# FPGA_PWR.net
KiCad netlist of a schematic drawn in Altium Designer
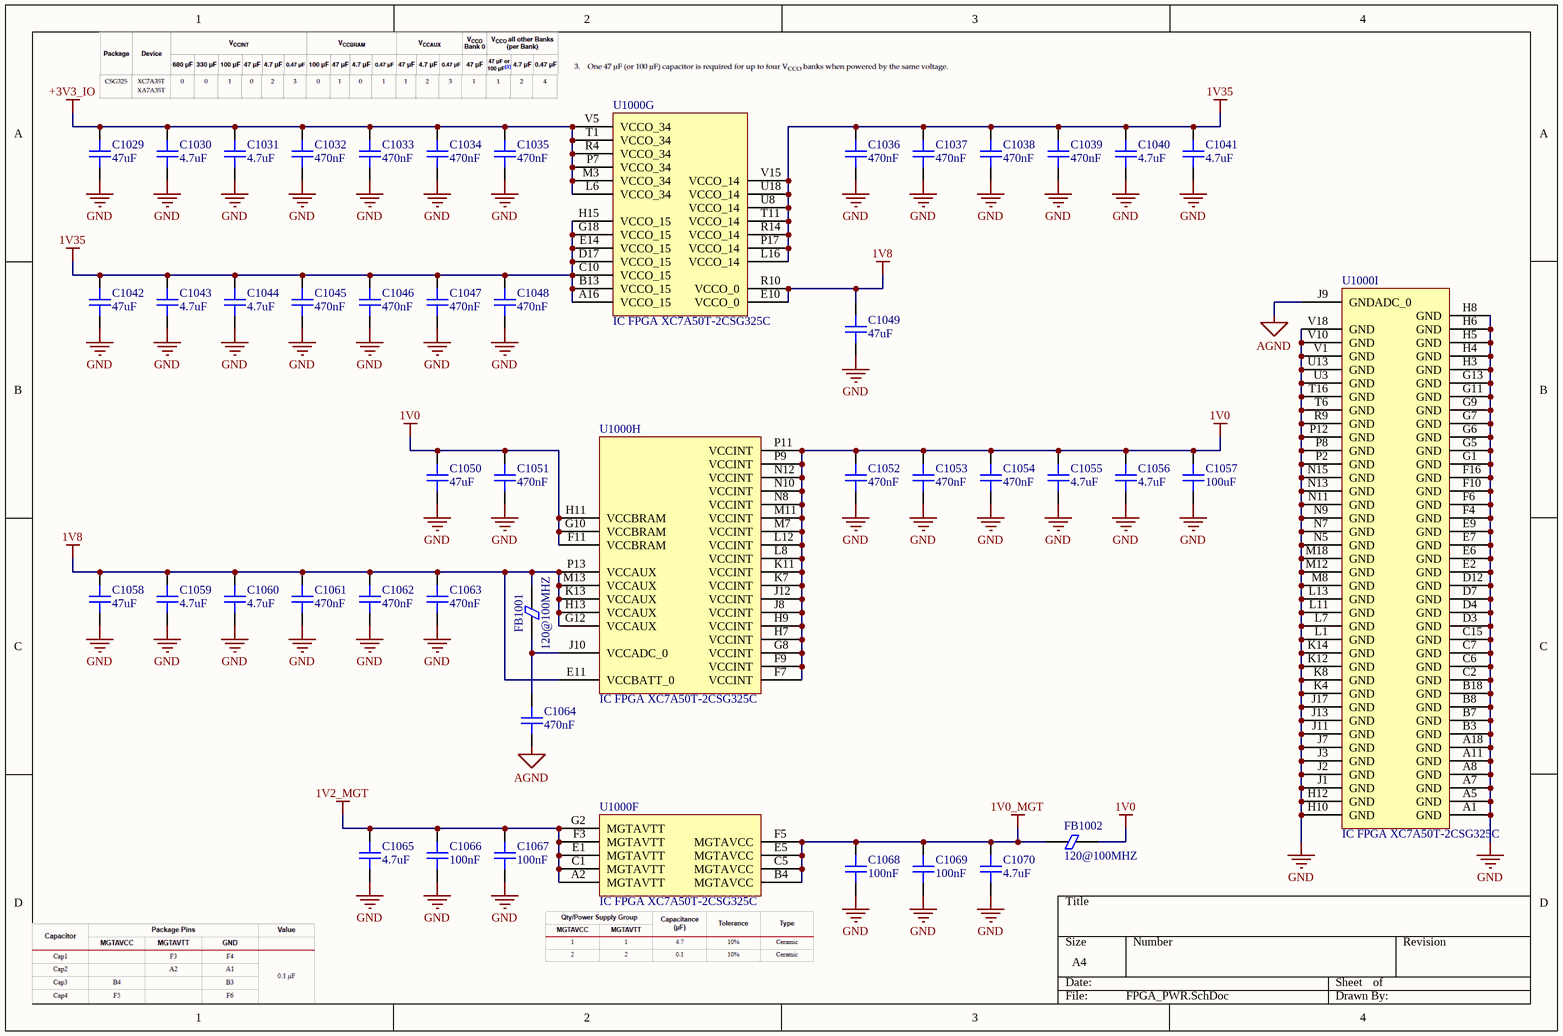
[diagram p0: FPGA_PWR.SchDoc]

(export (version "E")
  (design (tool "Eeschema 10.0.6"))
  (components
    (comp (ref "C1029")
      (value "47uF")
      (footprint "GEN_C_0805")
      (fields
        (field (name "HOUSE PART NUMBER") "C-47uF-0805-002")
        (field (name "MANUFACTURER") "Samsung")
        (field (name "MANUFACTURER PART NUMBER") "CL21A476MQYNNNE")
      )
      (libsource (lib "DSO") (part "CAP 47uF 6.3V X5R 0805"))
    )
    (comp (ref "C1030")
      (value "4.7uF")
      (footprint "GEN_C_0402")
      (fields
        (field (name "HOUSE PART NUMBER") "C-4.7uF-0402-002")
        (field (name "MANUFACTURER") "Murata")
        (field (name "MANUFACTURER PART NUMBER") "GRM155R60J475ME47D")
      )
      (libsource (lib "DSO") (part "CAP 4.7uF 6.3V X5R 0402"))
    )
    (comp (ref "C1031")
      (value "4.7uF")
      (footprint "GEN_C_0402")
      (fields
        (field (name "HOUSE PART NUMBER") "C-4.7uF-0402-002")
        (field (name "MANUFACTURER") "Murata")
        (field (name "MANUFACTURER PART NUMBER") "GRM155R60J475ME47D")
      )
      (libsource (lib "DSO") (part "CAP 4.7uF 6.3V X5R 0402"))
    )
    (comp (ref "C1032")
      (value "470nF")
      (footprint "GEN_C_0201")
      (fields
        (field (name "HOUSE PART NUMBER") "C-470nF-0201-002")
        (field (name "MANUFACTURER") "Murata")
        (field (name "MANUFACTURER PART NUMBER") "GRM033R60J474KE90D")
      )
      (libsource (lib "DSO") (part "CAP 470nF 6.3V X5R 0201"))
    )
    (comp (ref "C1033")
      (value "470nF")
      (footprint "GEN_C_0201")
      (fields
        (field (name "HOUSE PART NUMBER") "C-470nF-0201-002")
        (field (name "MANUFACTURER") "Murata")
        (field (name "MANUFACTURER PART NUMBER") "GRM033R60J474KE90D")
      )
      (libsource (lib "DSO") (part "CAP 470nF 6.3V X5R 0201"))
    )
    (comp (ref "C1034")
      (value "470nF")
      (footprint "GEN_C_0201")
      (fields
        (field (name "HOUSE PART NUMBER") "C-470nF-0201-002")
        (field (name "MANUFACTURER") "Murata")
        (field (name "MANUFACTURER PART NUMBER") "GRM033R60J474KE90D")
      )
      (libsource (lib "DSO") (part "CAP 470nF 6.3V X5R 0201"))
    )
    (comp (ref "C1035")
      (value "470nF")
      (footprint "GEN_C_0201")
      (fields
        (field (name "HOUSE PART NUMBER") "C-470nF-0201-002")
        (field (name "MANUFACTURER") "Murata")
        (field (name "MANUFACTURER PART NUMBER") "GRM033R60J474KE90D")
      )
      (libsource (lib "DSO") (part "CAP 470nF 6.3V X5R 0201"))
    )
    (comp (ref "C1036")
      (value "470nF")
      (footprint "GEN_C_0201")
      (fields
        (field (name "HOUSE PART NUMBER") "C-470nF-0201-002")
        (field (name "MANUFACTURER") "Murata")
        (field (name "MANUFACTURER PART NUMBER") "GRM033R60J474KE90D")
      )
      (libsource (lib "DSO") (part "CAP 470nF 6.3V X5R 0201"))
    )
    (comp (ref "C1037")
      (value "470nF")
      (footprint "GEN_C_0201")
      (fields
        (field (name "HOUSE PART NUMBER") "C-470nF-0201-002")
        (field (name "MANUFACTURER") "Murata")
        (field (name "MANUFACTURER PART NUMBER") "GRM033R60J474KE90D")
      )
      (libsource (lib "DSO") (part "CAP 470nF 6.3V X5R 0201"))
    )
    (comp (ref "C1038")
      (value "470nF")
      (footprint "GEN_C_0201")
      (fields
        (field (name "HOUSE PART NUMBER") "C-470nF-0201-002")
        (field (name "MANUFACTURER") "Murata")
        (field (name "MANUFACTURER PART NUMBER") "GRM033R60J474KE90D")
      )
      (libsource (lib "DSO") (part "CAP 470nF 6.3V X5R 0201"))
    )
    (comp (ref "C1039")
      (value "470nF")
      (footprint "GEN_C_0201")
      (fields
        (field (name "HOUSE PART NUMBER") "C-470nF-0201-002")
        (field (name "MANUFACTURER") "Murata")
        (field (name "MANUFACTURER PART NUMBER") "GRM033R60J474KE90D")
      )
      (libsource (lib "DSO") (part "CAP 470nF 6.3V X5R 0201"))
    )
    (comp (ref "C1040")
      (value "4.7uF")
      (footprint "GEN_C_0402")
      (fields
        (field (name "HOUSE PART NUMBER") "C-4.7uF-0402-002")
        (field (name "MANUFACTURER") "Murata")
        (field (name "MANUFACTURER PART NUMBER") "GRM155R60J475ME47D")
      )
      (libsource (lib "DSO") (part "CAP 4.7uF 6.3V X5R 0402"))
    )
    (comp (ref "C1041")
      (value "4.7uF")
      (footprint "GEN_C_0402")
      (fields
        (field (name "HOUSE PART NUMBER") "C-4.7uF-0402-002")
        (field (name "MANUFACTURER") "Murata")
        (field (name "MANUFACTURER PART NUMBER") "GRM155R60J475ME47D")
      )
      (libsource (lib "DSO") (part "CAP 4.7uF 6.3V X5R 0402"))
    )
    (comp (ref "C1042")
      (value "47uF")
      (footprint "GEN_C_0805")
      (fields
        (field (name "HOUSE PART NUMBER") "C-47uF-0805-002")
        (field (name "MANUFACTURER") "Samsung")
        (field (name "MANUFACTURER PART NUMBER") "CL21A476MQYNNNE")
      )
      (libsource (lib "DSO") (part "CAP 47uF 6.3V X5R 0805"))
    )
    (comp (ref "C1043")
      (value "4.7uF")
      (footprint "GEN_C_0402")
      (fields
        (field (name "HOUSE PART NUMBER") "C-4.7uF-0402-002")
        (field (name "MANUFACTURER") "Murata")
        (field (name "MANUFACTURER PART NUMBER") "GRM155R60J475ME47D")
      )
      (libsource (lib "DSO") (part "CAP 4.7uF 6.3V X5R 0402"))
    )
    (comp (ref "C1044")
      (value "4.7uF")
      (footprint "GEN_C_0402")
      (fields
        (field (name "HOUSE PART NUMBER") "C-4.7uF-0402-002")
        (field (name "MANUFACTURER") "Murata")
        (field (name "MANUFACTURER PART NUMBER") "GRM155R60J475ME47D")
      )
      (libsource (lib "DSO") (part "CAP 4.7uF 6.3V X5R 0402"))
    )
    (comp (ref "C1045")
      (value "470nF")
      (footprint "GEN_C_0201")
      (fields
        (field (name "HOUSE PART NUMBER") "C-470nF-0201-002")
        (field (name "MANUFACTURER") "Murata")
        (field (name "MANUFACTURER PART NUMBER") "GRM033R60J474KE90D")
      )
      (libsource (lib "DSO") (part "CAP 470nF 6.3V X5R 0201"))
    )
    (comp (ref "C1046")
      (value "470nF")
      (footprint "GEN_C_0201")
      (fields
        (field (name "HOUSE PART NUMBER") "C-470nF-0201-002")
        (field (name "MANUFACTURER") "Murata")
        (field (name "MANUFACTURER PART NUMBER") "GRM033R60J474KE90D")
      )
      (libsource (lib "DSO") (part "CAP 470nF 6.3V X5R 0201"))
    )
    (comp (ref "C1047")
      (value "470nF")
      (footprint "GEN_C_0201")
      (fields
        (field (name "HOUSE PART NUMBER") "C-470nF-0201-002")
        (field (name "MANUFACTURER") "Murata")
        (field (name "MANUFACTURER PART NUMBER") "GRM033R60J474KE90D")
      )
      (libsource (lib "DSO") (part "CAP 470nF 6.3V X5R 0201"))
    )
    (comp (ref "C1048")
      (value "470nF")
      (footprint "GEN_C_0201")
      (fields
        (field (name "HOUSE PART NUMBER") "C-470nF-0201-002")
        (field (name "MANUFACTURER") "Murata")
        (field (name "MANUFACTURER PART NUMBER") "GRM033R60J474KE90D")
      )
      (libsource (lib "DSO") (part "CAP 470nF 6.3V X5R 0201"))
    )
    (comp (ref "C1049")
      (value "47uF")
      (footprint "GEN_C_0805")
      (fields
        (field (name "HOUSE PART NUMBER") "C-47uF-0805-002")
        (field (name "MANUFACTURER") "Samsung")
        (field (name "MANUFACTURER PART NUMBER") "CL21A476MQYNNNE")
      )
      (libsource (lib "DSO") (part "CAP 47uF 6.3V X5R 0805"))
    )
    (comp (ref "C1050")
      (value "47uF")
      (footprint "GEN_C_0805")
      (fields
        (field (name "HOUSE PART NUMBER") "C-47uF-0805-002")
        (field (name "MANUFACTURER") "Samsung")
        (field (name "MANUFACTURER PART NUMBER") "CL21A476MQYNNNE")
      )
      (libsource (lib "DSO") (part "CAP 47uF 6.3V X5R 0805"))
    )
    (comp (ref "C1051")
      (value "470nF")
      (footprint "GEN_C_0201")
      (fields
        (field (name "HOUSE PART NUMBER") "C-470nF-0201-002")
        (field (name "MANUFACTURER") "Murata")
        (field (name "MANUFACTURER PART NUMBER") "GRM033R60J474KE90D")
      )
      (libsource (lib "DSO") (part "CAP 470nF 6.3V X5R 0201"))
    )
    (comp (ref "C1052")
      (value "470nF")
      (footprint "GEN_C_0201")
      (fields
        (field (name "HOUSE PART NUMBER") "C-470nF-0201-002")
        (field (name "MANUFACTURER") "Murata")
        (field (name "MANUFACTURER PART NUMBER") "GRM033R60J474KE90D")
      )
      (libsource (lib "DSO") (part "CAP 470nF 6.3V X5R 0201"))
    )
    (comp (ref "C1053")
      (value "470nF")
      (footprint "GEN_C_0201")
      (fields
        (field (name "HOUSE PART NUMBER") "C-470nF-0201-002")
        (field (name "MANUFACTURER") "Murata")
        (field (name "MANUFACTURER PART NUMBER") "GRM033R60J474KE90D")
      )
      (libsource (lib "DSO") (part "CAP 470nF 6.3V X5R 0201"))
    )
    (comp (ref "C1054")
      (value "470nF")
      (footprint "GEN_C_0201")
      (fields
        (field (name "HOUSE PART NUMBER") "C-470nF-0201-002")
        (field (name "MANUFACTURER") "Murata")
        (field (name "MANUFACTURER PART NUMBER") "GRM033R60J474KE90D")
      )
      (libsource (lib "DSO") (part "CAP 470nF 6.3V X5R 0201"))
    )
    (comp (ref "C1055")
      (value "4.7uF")
      (footprint "GEN_C_0402")
      (fields
        (field (name "HOUSE PART NUMBER") "C-4.7uF-0402-002")
        (field (name "MANUFACTURER") "Murata")
        (field (name "MANUFACTURER PART NUMBER") "GRM155R60J475ME47D")
      )
      (libsource (lib "DSO") (part "CAP 4.7uF 6.3V X5R 0402"))
    )
    (comp (ref "C1056")
      (value "4.7uF")
      (footprint "GEN_C_0402")
      (fields
        (field (name "HOUSE PART NUMBER") "C-4.7uF-0402-002")
        (field (name "MANUFACTURER") "Murata")
        (field (name "MANUFACTURER PART NUMBER") "GRM155R60J475ME47D")
      )
      (libsource (lib "DSO") (part "CAP 4.7uF 6.3V X5R 0402"))
    )
    (comp (ref "C1057")
      (value "100uF")
      (footprint "GEN_C_1210")
      (fields
        (field (name "HOUSE PART NUMBER") "C-100uF-1210-002")
        (field (name "MANUFACTURER") "Samsung")
        (field (name "MANUFACTURER PART NUMBER") "CL32A107MQVNNNE")
      )
      (libsource (lib "DSO") (part "CAP 100uF 6.3V X5R 1210"))
    )
    (comp (ref "C1058")
      (value "47uF")
      (footprint "GEN_C_0805")
      (fields
        (field (name "HOUSE PART NUMBER") "C-47uF-0805-002")
        (field (name "MANUFACTURER") "Samsung")
        (field (name "MANUFACTURER PART NUMBER") "CL21A476MQYNNNE")
      )
      (libsource (lib "DSO") (part "CAP 47uF 6.3V X5R 0805"))
    )
    (comp (ref "C1059")
      (value "4.7uF")
      (footprint "GEN_C_0402")
      (fields
        (field (name "HOUSE PART NUMBER") "C-4.7uF-0402-002")
        (field (name "MANUFACTURER") "Murata")
        (field (name "MANUFACTURER PART NUMBER") "GRM155R60J475ME47D")
      )
      (libsource (lib "DSO") (part "CAP 4.7uF 6.3V X5R 0402"))
    )
    (comp (ref "C1060")
      (value "4.7uF")
      (footprint "GEN_C_0402")
      (fields
        (field (name "HOUSE PART NUMBER") "C-4.7uF-0402-002")
        (field (name "MANUFACTURER") "Murata")
        (field (name "MANUFACTURER PART NUMBER") "GRM155R60J475ME47D")
      )
      (libsource (lib "DSO") (part "CAP 4.7uF 6.3V X5R 0402"))
    )
    (comp (ref "C1061")
      (value "470nF")
      (footprint "GEN_C_0201")
      (fields
        (field (name "HOUSE PART NUMBER") "C-470nF-0201-002")
        (field (name "MANUFACTURER") "Murata")
        (field (name "MANUFACTURER PART NUMBER") "GRM033R60J474KE90D")
      )
      (libsource (lib "DSO") (part "CAP 470nF 6.3V X5R 0201"))
    )
    (comp (ref "C1062")
      (value "470nF")
      (footprint "GEN_C_0201")
      (fields
        (field (name "HOUSE PART NUMBER") "C-470nF-0201-002")
        (field (name "MANUFACTURER") "Murata")
        (field (name "MANUFACTURER PART NUMBER") "GRM033R60J474KE90D")
      )
      (libsource (lib "DSO") (part "CAP 470nF 6.3V X5R 0201"))
    )
    (comp (ref "C1063")
      (value "470nF")
      (footprint "GEN_C_0201")
      (fields
        (field (name "HOUSE PART NUMBER") "C-470nF-0201-002")
        (field (name "MANUFACTURER") "Murata")
        (field (name "MANUFACTURER PART NUMBER") "GRM033R60J474KE90D")
      )
      (libsource (lib "DSO") (part "CAP 470nF 6.3V X5R 0201"))
    )
    (comp (ref "C1064")
      (value "470nF")
      (footprint "GEN_C_0201")
      (fields
        (field (name "HOUSE PART NUMBER") "C-470nF-0201-002")
        (field (name "MANUFACTURER") "Murata")
        (field (name "MANUFACTURER PART NUMBER") "GRM033R60J474KE90D")
      )
      (libsource (lib "DSO") (part "CAP 470nF 6.3V X5R 0201"))
    )
    (comp (ref "C1065")
      (value "4.7uF")
      (footprint "GEN_C_0402")
      (fields
        (field (name "HOUSE PART NUMBER") "C-4.7uF-0402-002")
        (field (name "MANUFACTURER") "Murata")
        (field (name "MANUFACTURER PART NUMBER") "GRM155R60J475ME47D")
      )
      (libsource (lib "DSO") (part "CAP 4.7uF 6.3V X5R 0402"))
    )
    (comp (ref "C1066")
      (value "100nF")
      (footprint "GEN_C_0201")
      (fields
        (field (name "HOUSE PART NUMBER") "C-100nF-0201-002")
        (field (name "MANUFACTURER") "Murata")
        (field (name "MANUFACTURER PART NUMBER") "GRM033R60J104KE19D")
      )
      (libsource (lib "DSO") (part "CAP 100nF 6.3V X5R 0201"))
    )
    (comp (ref "C1067")
      (value "100nF")
      (footprint "GEN_C_0201")
      (fields
        (field (name "HOUSE PART NUMBER") "C-100nF-0201-002")
        (field (name "MANUFACTURER") "Murata")
        (field (name "MANUFACTURER PART NUMBER") "GRM033R60J104KE19D")
      )
      (libsource (lib "DSO") (part "CAP 100nF 6.3V X5R 0201"))
    )
    (comp (ref "C1068")
      (value "100nF")
      (footprint "GEN_C_0201")
      (fields
        (field (name "HOUSE PART NUMBER") "C-100nF-0201-002")
        (field (name "MANUFACTURER") "Murata")
        (field (name "MANUFACTURER PART NUMBER") "GRM033R60J104KE19D")
      )
      (libsource (lib "DSO") (part "CAP 100nF 6.3V X5R 0201"))
    )
    (comp (ref "C1069")
      (value "100nF")
      (footprint "GEN_C_0201")
      (fields
        (field (name "HOUSE PART NUMBER") "C-100nF-0201-002")
        (field (name "MANUFACTURER") "Murata")
        (field (name "MANUFACTURER PART NUMBER") "GRM033R60J104KE19D")
      )
      (libsource (lib "DSO") (part "CAP 100nF 6.3V X5R 0201"))
    )
    (comp (ref "C1070")
      (value "4.7uF")
      (footprint "GEN_C_0402")
      (fields
        (field (name "HOUSE PART NUMBER") "C-4.7uF-0402-002")
        (field (name "MANUFACTURER") "Murata")
        (field (name "MANUFACTURER PART NUMBER") "GRM155R60J475ME47D")
      )
      (libsource (lib "DSO") (part "CAP 4.7uF 6.3V X5R 0402"))
    )
    (comp (ref "FB1001")
      (value "120@100MHZ")
      (footprint "GEN_R_0402")
      (fields (field (name "HOUSE PART NUMBER") "BLM15PX121SN1D") (field (name "MANUFACTURER") "Murata"))
      (libsource (lib "DSO") (part "FERRITE BEAD 120 OHM 0402"))
    )
    (comp (ref "FB1002")
      (value "120@100MHZ")
      (footprint "GEN_R_0402")
      (fields (field (name "HOUSE PART NUMBER") "BLM15PX121SN1D") (field (name "MANUFACTURER") "Murata"))
      (libsource (lib "DSO") (part "FERRITE BEAD 120 OHM 0402"))
    )
    (comp (ref "U1000")
      (value "IC FPGA XC7A50T-2CSG325C")
      (footprint "XILINX_XC7A50T-2CSG325C")
      (description "Artix-7 FPGA, 150 User I/Os, 4 GTP, 324-Ball BGA, Speed Grade 2, Commercial Grade, Pb-Free")
      (fields (field (name "MANUFACTURER") "Xilinx") (field (name "HOUSE PART NUMBER") "XC7A50T-2CSG325C"))
      (libsource (lib "DSO") (part "IC FPGA XC7A50T-2CSG325C"))
    )
  )
  (nets
    (net (code "1") (name "+3V3_IO") (class "Default")
      (node (ref "C1029") (pin "2") (pinfunction "2_2") (pintype "passive"))
      (node (ref "C1030") (pin "2") (pinfunction "2_2") (pintype "passive"))
      (node (ref "C1031") (pin "2") (pinfunction "2_2") (pintype "passive"))
      (node (ref "C1032") (pin "2") (pinfunction "2_2") (pintype "passive"))
      (node (ref "C1033") (pin "2") (pinfunction "2_2") (pintype "passive"))
      (node (ref "C1034") (pin "2") (pinfunction "2_2") (pintype "passive"))
      (node (ref "C1035") (pin "2") (pinfunction "2_2") (pintype "passive"))
      (node (ref "U1000") (pin "L6") (pinfunction "VCCO_34_L6") (pintype "power_in"))
      (node (ref "U1000") (pin "M3") (pinfunction "VCCO_34_M3") (pintype "power_in"))
      (node (ref "U1000") (pin "P7") (pinfunction "VCCO_34_P7") (pintype "power_in"))
      (node (ref "U1000") (pin "R4") (pinfunction "VCCO_34_R4") (pintype "power_in"))
      (node (ref "U1000") (pin "T1") (pinfunction "VCCO_34_T1") (pintype "power_in"))
      (node (ref "U1000") (pin "V5") (pinfunction "VCCO_34_V5") (pintype "power_in"))
    )
    (net (code "2") (name "1V0") (class "Default")
      (node (ref "C1050") (pin "2") (pinfunction "2_2") (pintype "passive"))
      (node (ref "C1051") (pin "2") (pinfunction "2_2") (pintype "passive"))
      (node (ref "C1052") (pin "2") (pinfunction "2_2") (pintype "passive"))
      (node (ref "C1053") (pin "2") (pinfunction "2_2") (pintype "passive"))
      (node (ref "C1054") (pin "2") (pinfunction "2_2") (pintype "passive"))
      (node (ref "C1055") (pin "2") (pinfunction "2_2") (pintype "passive"))
      (node (ref "C1056") (pin "2") (pinfunction "2_2") (pintype "passive"))
      (node (ref "C1057") (pin "2") (pinfunction "2_2") (pintype "passive"))
      (node (ref "FB1002") (pin "1") (pinfunction "1_1") (pintype "passive"))
      (node (ref "U1000") (pin "F11") (pinfunction "VCCBRAM_F11") (pintype "power_in"))
      (node (ref "U1000") (pin "F7") (pinfunction "VCCINT_F7") (pintype "power_in"))
      (node (ref "U1000") (pin "F9") (pinfunction "VCCINT_F9") (pintype "power_in"))
      (node (ref "U1000") (pin "G10") (pinfunction "VCCBRAM_G10") (pintype "power_in"))
      (node (ref "U1000") (pin "G8") (pinfunction "VCCINT_G8") (pintype "power_in"))
      (node (ref "U1000") (pin "H11") (pinfunction "VCCBRAM_H11") (pintype "power_in"))
      (node (ref "U1000") (pin "H7") (pinfunction "VCCINT_H7") (pintype "power_in"))
      (node (ref "U1000") (pin "H9") (pinfunction "VCCINT_H9") (pintype "power_in"))
      (node (ref "U1000") (pin "J12") (pinfunction "VCCINT_J12") (pintype "power_in"))
      (node (ref "U1000") (pin "J8") (pinfunction "VCCINT_J8") (pintype "power_in"))
      (node (ref "U1000") (pin "K11") (pinfunction "VCCINT_K11") (pintype "power_in"))
      (node (ref "U1000") (pin "K7") (pinfunction "VCCINT_K7") (pintype "power_in"))
      (node (ref "U1000") (pin "L12") (pinfunction "VCCINT_L12") (pintype "power_in"))
      (node (ref "U1000") (pin "L8") (pinfunction "VCCINT_L8") (pintype "power_in"))
      (node (ref "U1000") (pin "M11") (pinfunction "VCCINT_M11") (pintype "power_in"))
      (node (ref "U1000") (pin "M7") (pinfunction "VCCINT_M7") (pintype "power_in"))
      (node (ref "U1000") (pin "N10") (pinfunction "VCCINT_N10") (pintype "power_in"))
      (node (ref "U1000") (pin "N12") (pinfunction "VCCINT_N12") (pintype "power_in"))
      (node (ref "U1000") (pin "N8") (pinfunction "VCCINT_N8") (pintype "power_in"))
      (node (ref "U1000") (pin "P11") (pinfunction "VCCINT_P11") (pintype "power_in"))
      (node (ref "U1000") (pin "P9") (pinfunction "VCCINT_P9") (pintype "power_in"))
    )
    (net (code "3") (name "1V0_MGT") (class "Default")
      (node (ref "C1068") (pin "2") (pinfunction "2_2") (pintype "passive"))
      (node (ref "C1069") (pin "2") (pinfunction "2_2") (pintype "passive"))
      (node (ref "C1070") (pin "2") (pinfunction "2_2") (pintype "passive"))
      (node (ref "FB1002") (pin "2") (pinfunction "2_2") (pintype "passive"))
      (node (ref "U1000") (pin "B4") (pinfunction "MGTAVCC_B4") (pintype "power_in"))
      (node (ref "U1000") (pin "C5") (pinfunction "MGTAVCC_C5") (pintype "power_in"))
      (node (ref "U1000") (pin "E5") (pinfunction "MGTAVCC_E5") (pintype "power_in"))
      (node (ref "U1000") (pin "F5") (pinfunction "MGTAVCC_F5") (pintype "power_in"))
    )
    (net (code "4") (name "1V2_MGT") (class "Default")
      (node (ref "C1065") (pin "2") (pinfunction "2_2") (pintype "passive"))
      (node (ref "C1066") (pin "2") (pinfunction "2_2") (pintype "passive"))
      (node (ref "C1067") (pin "2") (pinfunction "2_2") (pintype "passive"))
      (node (ref "U1000") (pin "A2") (pinfunction "MGTAVTT_A2") (pintype "power_in"))
      (node (ref "U1000") (pin "C1") (pinfunction "MGTAVTT_C1") (pintype "power_in"))
      (node (ref "U1000") (pin "E1") (pinfunction "MGTAVTT_E1") (pintype "power_in"))
      (node (ref "U1000") (pin "F3") (pinfunction "MGTAVTT_F3") (pintype "power_in"))
      (node (ref "U1000") (pin "G2") (pinfunction "MGTAVTT_G2") (pintype "power_in"))
    )
    (net (code "5") (name "1V8") (class "Default")
      (node (ref "C1049") (pin "2") (pinfunction "2_2") (pintype "passive"))
      (node (ref "C1058") (pin "2") (pinfunction "2_2") (pintype "passive"))
      (node (ref "C1059") (pin "2") (pinfunction "2_2") (pintype "passive"))
      (node (ref "C1060") (pin "2") (pinfunction "2_2") (pintype "passive"))
      (node (ref "C1061") (pin "2") (pinfunction "2_2") (pintype "passive"))
      (node (ref "C1062") (pin "2") (pinfunction "2_2") (pintype "passive"))
      (node (ref "C1063") (pin "2") (pinfunction "2_2") (pintype "passive"))
      (node (ref "FB1001") (pin "2") (pinfunction "2_2") (pintype "passive"))
      (node (ref "U1000") (pin "E10") (pinfunction "VCCO_0_E10") (pintype "power_in"))
      (node (ref "U1000") (pin "E11") (pinfunction "VCCBATT_0_E11") (pintype "power_in"))
      (node (ref "U1000") (pin "G12") (pinfunction "VCCAUX_G12") (pintype "power_in"))
      (node (ref "U1000") (pin "H13") (pinfunction "VCCAUX_H13") (pintype "power_in"))
      (node (ref "U1000") (pin "K13") (pinfunction "VCCAUX_K13") (pintype "power_in"))
      (node (ref "U1000") (pin "M13") (pinfunction "VCCAUX_M13") (pintype "power_in"))
      (node (ref "U1000") (pin "P13") (pinfunction "VCCAUX_P13") (pintype "power_in"))
      (node (ref "U1000") (pin "R10") (pinfunction "VCCO_0_R10") (pintype "power_in"))
    )
    (net (code "6") (name "1V35") (class "Default")
      (node (ref "C1036") (pin "2") (pinfunction "2_2") (pintype "passive"))
      (node (ref "C1037") (pin "2") (pinfunction "2_2") (pintype "passive"))
      (node (ref "C1038") (pin "2") (pinfunction "2_2") (pintype "passive"))
      (node (ref "C1039") (pin "2") (pinfunction "2_2") (pintype "passive"))
      (node (ref "C1040") (pin "2") (pinfunction "2_2") (pintype "passive"))
      (node (ref "C1041") (pin "2") (pinfunction "2_2") (pintype "passive"))
      (node (ref "C1042") (pin "2") (pinfunction "2_2") (pintype "passive"))
      (node (ref "C1043") (pin "2") (pinfunction "2_2") (pintype "passive"))
      (node (ref "C1044") (pin "2") (pinfunction "2_2") (pintype "passive"))
      (node (ref "C1045") (pin "2") (pinfunction "2_2") (pintype "passive"))
      (node (ref "C1046") (pin "2") (pinfunction "2_2") (pintype "passive"))
      (node (ref "C1047") (pin "2") (pinfunction "2_2") (pintype "passive"))
      (node (ref "C1048") (pin "2") (pinfunction "2_2") (pintype "passive"))
      (node (ref "U1000") (pin "A16") (pinfunction "VCCO_15_A16") (pintype "power_in"))
      (node (ref "U1000") (pin "B13") (pinfunction "VCCO_15_B13") (pintype "power_in"))
      (node (ref "U1000") (pin "C10") (pinfunction "VCCO_15_C10") (pintype "power_in"))
      (node (ref "U1000") (pin "D17") (pinfunction "VCCO_15_D17") (pintype "power_in"))
      (node (ref "U1000") (pin "E14") (pinfunction "VCCO_15_E14") (pintype "power_in"))
      (node (ref "U1000") (pin "G18") (pinfunction "VCCO_15_G18") (pintype "power_in"))
      (node (ref "U1000") (pin "H15") (pinfunction "VCCO_15_H15") (pintype "power_in"))
      (node (ref "U1000") (pin "L16") (pinfunction "VCCO_14_L16") (pintype "power_in"))
      (node (ref "U1000") (pin "P17") (pinfunction "VCCO_14_P17") (pintype "power_in"))
      (node (ref "U1000") (pin "R14") (pinfunction "VCCO_14_R14") (pintype "power_in"))
      (node (ref "U1000") (pin "T11") (pinfunction "VCCO_14_T11") (pintype "power_in"))
      (node (ref "U1000") (pin "U18") (pinfunction "VCCO_14_U18") (pintype "power_in"))
      (node (ref "U1000") (pin "U8") (pinfunction "VCCO_14_U8") (pintype "power_in"))
      (node (ref "U1000") (pin "V15") (pinfunction "VCCO_14_V15") (pintype "power_in"))
    )
    (net (code "7") (name "AGND") (class "Default")
      (node (ref "C1064") (pin "1") (pinfunction "1_1") (pintype "passive"))
      (node (ref "U1000") (pin "J9") (pinfunction "GNDADC_0_J9") (pintype "power_in"))
    )
    (net (code "8") (name "GND") (class "Default")
      (node (ref "C1029") (pin "1") (pinfunction "1_1") (pintype "passive"))
      (node (ref "C1030") (pin "1") (pinfunction "1_1") (pintype "passive"))
      (node (ref "C1031") (pin "1") (pinfunction "1_1") (pintype "passive"))
      (node (ref "C1032") (pin "1") (pinfunction "1_1") (pintype "passive"))
      (node (ref "C1033") (pin "1") (pinfunction "1_1") (pintype "passive"))
      (node (ref "C1034") (pin "1") (pinfunction "1_1") (pintype "passive"))
      (node (ref "C1035") (pin "1") (pinfunction "1_1") (pintype "passive"))
      (node (ref "C1036") (pin "1") (pinfunction "1_1") (pintype "passive"))
      (node (ref "C1037") (pin "1") (pinfunction "1_1") (pintype "passive"))
      (node (ref "C1038") (pin "1") (pinfunction "1_1") (pintype "passive"))
      (node (ref "C1039") (pin "1") (pinfunction "1_1") (pintype "passive"))
      (node (ref "C1040") (pin "1") (pinfunction "1_1") (pintype "passive"))
      (node (ref "C1041") (pin "1") (pinfunction "1_1") (pintype "passive"))
      (node (ref "C1042") (pin "1") (pinfunction "1_1") (pintype "passive"))
      (node (ref "C1043") (pin "1") (pinfunction "1_1") (pintype "passive"))
      (node (ref "C1044") (pin "1") (pinfunction "1_1") (pintype "passive"))
      (node (ref "C1045") (pin "1") (pinfunction "1_1") (pintype "passive"))
      (node (ref "C1046") (pin "1") (pinfunction "1_1") (pintype "passive"))
      (node (ref "C1047") (pin "1") (pinfunction "1_1") (pintype "passive"))
      (node (ref "C1048") (pin "1") (pinfunction "1_1") (pintype "passive"))
      (node (ref "C1049") (pin "1") (pinfunction "1_1") (pintype "passive"))
      (node (ref "C1050") (pin "1") (pinfunction "1_1") (pintype "passive"))
      (node (ref "C1051") (pin "1") (pinfunction "1_1") (pintype "passive"))
      (node (ref "C1052") (pin "1") (pinfunction "1_1") (pintype "passive"))
      (node (ref "C1053") (pin "1") (pinfunction "1_1") (pintype "passive"))
      (node (ref "C1054") (pin "1") (pinfunction "1_1") (pintype "passive"))
      (node (ref "C1055") (pin "1") (pinfunction "1_1") (pintype "passive"))
      (node (ref "C1056") (pin "1") (pinfunction "1_1") (pintype "passive"))
      (node (ref "C1057") (pin "1") (pinfunction "1_1") (pintype "passive"))
      (node (ref "C1058") (pin "1") (pinfunction "1_1") (pintype "passive"))
      (node (ref "C1059") (pin "1") (pinfunction "1_1") (pintype "passive"))
      (node (ref "C1060") (pin "1") (pinfunction "1_1") (pintype "passive"))
      (node (ref "C1061") (pin "1") (pinfunction "1_1") (pintype "passive"))
      (node (ref "C1062") (pin "1") (pinfunction "1_1") (pintype "passive"))
      (node (ref "C1063") (pin "1") (pinfunction "1_1") (pintype "passive"))
      (node (ref "C1065") (pin "1") (pinfunction "1_1") (pintype "passive"))
      (node (ref "C1066") (pin "1") (pinfunction "1_1") (pintype "passive"))
      (node (ref "C1067") (pin "1") (pinfunction "1_1") (pintype "passive"))
      (node (ref "C1068") (pin "1") (pinfunction "1_1") (pintype "passive"))
      (node (ref "C1069") (pin "1") (pinfunction "1_1") (pintype "passive"))
      (node (ref "C1070") (pin "1") (pinfunction "1_1") (pintype "passive"))
      (node (ref "U1000") (pin "A1") (pinfunction "GND_A1") (pintype "power_in"))
      (node (ref "U1000") (pin "A11") (pinfunction "GND_A11") (pintype "power_in"))
      (node (ref "U1000") (pin "A18") (pinfunction "GND_A18") (pintype "power_in"))
      (node (ref "U1000") (pin "A5") (pinfunction "GND_A5") (pintype "power_in"))
      (node (ref "U1000") (pin "A7") (pinfunction "GND_A7") (pintype "power_in"))
      (node (ref "U1000") (pin "A8") (pinfunction "GND_A8") (pintype "power_in"))
      (node (ref "U1000") (pin "B18") (pinfunction "GND_B18") (pintype "power_in"))
      (node (ref "U1000") (pin "B3") (pinfunction "GND_B3") (pintype "power_in"))
      (node (ref "U1000") (pin "B7") (pinfunction "GND_B7") (pintype "power_in"))
      (node (ref "U1000") (pin "B8") (pinfunction "GND_B8") (pintype "power_in"))
      (node (ref "U1000") (pin "C15") (pinfunction "GND_C15") (pintype "power_in"))
      (node (ref "U1000") (pin "C2") (pinfunction "GND_C2") (pintype "power_in"))
      (node (ref "U1000") (pin "C6") (pinfunction "GND_C6") (pintype "power_in"))
      (node (ref "U1000") (pin "C7") (pinfunction "GND_C7") (pintype "power_in"))
      (node (ref "U1000") (pin "D12") (pinfunction "GND_D12") (pintype "power_in"))
      (node (ref "U1000") (pin "D3") (pinfunction "GND_D3") (pintype "power_in"))
      (node (ref "U1000") (pin "D4") (pinfunction "GND_D4") (pintype "power_in"))
      (node (ref "U1000") (pin "D7") (pinfunction "GND_D7") (pintype "power_in"))
      (node (ref "U1000") (pin "E2") (pinfunction "GND_E2") (pintype "power_in"))
      (node (ref "U1000") (pin "E6") (pinfunction "GND_E6") (pintype "power_in"))
      (node (ref "U1000") (pin "E7") (pinfunction "GND_E7") (pintype "power_in"))
      (node (ref "U1000") (pin "E9") (pinfunction "GND_E9") (pintype "power_in"))
      (node (ref "U1000") (pin "F10") (pinfunction "GND_F10") (pintype "power_in"))
      (node (ref "U1000") (pin "F16") (pinfunction "GND_F16") (pintype "power_in"))
      (node (ref "U1000") (pin "F4") (pinfunction "GND_F4") (pintype "power_in"))
      (node (ref "U1000") (pin "F6") (pinfunction "GND_F6") (pintype "power_in"))
      (node (ref "U1000") (pin "G1") (pinfunction "GND_G1") (pintype "power_in"))
      (node (ref "U1000") (pin "G11") (pinfunction "GND_G11") (pintype "power_in"))
      (node (ref "U1000") (pin "G13") (pinfunction "GND_G13") (pintype "power_in"))
      (node (ref "U1000") (pin "G5") (pinfunction "GND_G5") (pintype "power_in"))
      (node (ref "U1000") (pin "G6") (pinfunction "GND_G6") (pintype "power_in"))
      (node (ref "U1000") (pin "G7") (pinfunction "GND_G7") (pintype "power_in"))
      (node (ref "U1000") (pin "G9") (pinfunction "GND_G9") (pintype "power_in"))
      (node (ref "U1000") (pin "H10") (pinfunction "GND_H10") (pintype "power_in"))
      (node (ref "U1000") (pin "H12") (pinfunction "GND_H12") (pintype "power_in"))
      (node (ref "U1000") (pin "H3") (pinfunction "GND_H3") (pintype "power_in"))
      (node (ref "U1000") (pin "H4") (pinfunction "GND_H4") (pintype "power_in"))
      (node (ref "U1000") (pin "H5") (pinfunction "GND_H5") (pintype "power_in"))
      (node (ref "U1000") (pin "H6") (pinfunction "GND_H6") (pintype "power_in"))
      (node (ref "U1000") (pin "H8") (pinfunction "GND_H8") (pintype "power_in"))
      (node (ref "U1000") (pin "J1") (pinfunction "GND_J1") (pintype "power_in"))
      (node (ref "U1000") (pin "J11") (pinfunction "GND_J11") (pintype "power_in"))
      (node (ref "U1000") (pin "J13") (pinfunction "GND_J13") (pintype "power_in"))
      (node (ref "U1000") (pin "J17") (pinfunction "GND_J17") (pintype "power_in"))
      (node (ref "U1000") (pin "J2") (pinfunction "GND_J2") (pintype "power_in"))
      (node (ref "U1000") (pin "J3") (pinfunction "GND_J3") (pintype "power_in"))
      (node (ref "U1000") (pin "J7") (pinfunction "GND_J7") (pintype "power_in"))
      (node (ref "U1000") (pin "K12") (pinfunction "GND_K12") (pintype "power_in"))
      (node (ref "U1000") (pin "K14") (pinfunction "GND_K14") (pintype "power_in"))
      (node (ref "U1000") (pin "K4") (pinfunction "GND_K4") (pintype "power_in"))
      (node (ref "U1000") (pin "K8") (pinfunction "GND_K8") (pintype "power_in"))
      (node (ref "U1000") (pin "L1") (pinfunction "GND_L1") (pintype "power_in"))
      (node (ref "U1000") (pin "L11") (pinfunction "GND_L11") (pintype "power_in"))
      (node (ref "U1000") (pin "L13") (pinfunction "GND_L13") (pintype "power_in"))
      (node (ref "U1000") (pin "L7") (pinfunction "GND_L7") (pintype "power_in"))
      (node (ref "U1000") (pin "M12") (pinfunction "GND_M12") (pintype "power_in"))
      (node (ref "U1000") (pin "M18") (pinfunction "GND_M18") (pintype "power_in"))
      (node (ref "U1000") (pin "M8") (pinfunction "GND_M8") (pintype "power_in"))
      (node (ref "U1000") (pin "N11") (pinfunction "GND_N11") (pintype "power_in"))
      (node (ref "U1000") (pin "N13") (pinfunction "GND_N13") (pintype "power_in"))
      (node (ref "U1000") (pin "N15") (pinfunction "GND_N15") (pintype "power_in"))
      (node (ref "U1000") (pin "N5") (pinfunction "GND_N5") (pintype "power_in"))
      (node (ref "U1000") (pin "N7") (pinfunction "GND_N7") (pintype "power_in"))
      (node (ref "U1000") (pin "N9") (pinfunction "GND_N9") (pintype "power_in"))
      (node (ref "U1000") (pin "P12") (pinfunction "GND_P12") (pintype "power_in"))
      (node (ref "U1000") (pin "P2") (pinfunction "GND_P2") (pintype "power_in"))
      (node (ref "U1000") (pin "P8") (pinfunction "GND_P8") (pintype "power_in"))
      (node (ref "U1000") (pin "R9") (pinfunction "GND_R9") (pintype "power_in"))
      (node (ref "U1000") (pin "T16") (pinfunction "GND_T16") (pintype "power_in"))
      (node (ref "U1000") (pin "T6") (pinfunction "GND_T6") (pintype "power_in"))
      (node (ref "U1000") (pin "U13") (pinfunction "GND_U13") (pintype "power_in"))
      (node (ref "U1000") (pin "U3") (pinfunction "GND_U3") (pintype "power_in"))
      (node (ref "U1000") (pin "V1") (pinfunction "GND_V1") (pintype "power_in"))
      (node (ref "U1000") (pin "V10") (pinfunction "GND_V10") (pintype "power_in"))
      (node (ref "U1000") (pin "V18") (pinfunction "GND_V18") (pintype "power_in"))
    )
    (net (code "9") (name "Net-(U1000H-VCCADC_0)") (class "Default")
      (node (ref "C1064") (pin "2") (pinfunction "2_2") (pintype "passive"))
      (node (ref "FB1001") (pin "1") (pinfunction "1_1") (pintype "passive"))
      (node (ref "U1000") (pin "J10") (pinfunction "VCCADC_0_J10") (pintype "power_in"))
    )
  )
)
